# DM35_Power_C_V1_0.net
KiCad netlist of a schematic drawn in Altium Designer
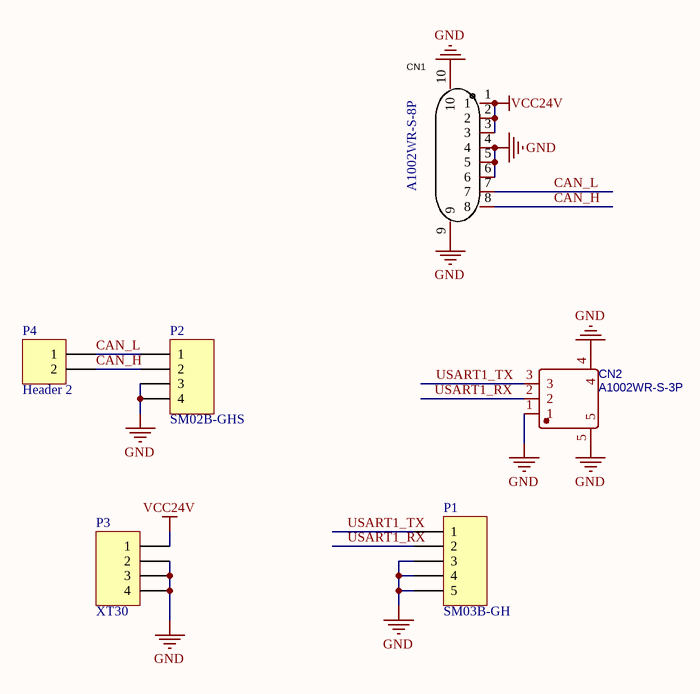
[diagram p0: DM35_Power_C_V1.0.SchDoc]

(export (version "E")
  (design (tool "Eeschema 10.0.6"))
  (components
    (comp (ref "CN1")
      (value "A1002WR-S-8P")
      (footprint "CONN-SMD_A1002WR-S-8P")
      (fields (field (name "MANUFACTURER") "CJT(长江连接器)"))
      (libsource (lib "dm-sch_library") (part "A1002WR-S-8P"))
    )
    (comp (ref "CN2")
      (value "A1002WR-S-3P")
      (footprint "CONN-SMD_A1002WR-S-3P")
      (fields (field (name "BOM_SUPPLIER PART") "C239521") (field (name "CONTRIBUTOR") "LCSC"))
      (libsource (lib "dm-sch_library") (part "A1002WR-S-3P"))
    )
    (comp (ref "P1")
      (value "SM03B-GH")
      (footprint "JST SM03B-GHS-TB")
      (description "Header, 5-Pin")
      (fields (field (name "PUBLISHER") "Altium Limited"))
      (libsource (lib "Miscellaneous Connectors") (part "Header 5"))
    )
    (comp (ref "P2")
      (value "SM02B-GHS")
      (footprint "JST-SM02B-GHS-TB")
      (description "Header, 4-Pin")
      (fields (field (name "PUBLISHER") "Altium Limited"))
      (libsource (lib "Miscellaneous Connectors") (part "Header 4"))
    )
    (comp (ref "P3")
      (value "XT30")
      (footprint "XT30PW-M")
      (description "Header, 4-Pin")
      (fields (field (name "PUBLISHER") "Altium Limited"))
      (libsource (lib "") (part "Header 4_1"))
    )
    (comp (ref "P4")
      (value "Header 2")
      (footprint "HDR1X2")
      (description "Header, 2-Pin")
      (fields (field (name "PUBLISHER") "Altium Limited"))
      (libsource (lib "Miscellaneous Connectors") (part "Header 2"))
    )
  )
  (nets
    (net (code "1") (name "/CAN_H") (class "Default")
      (node (ref "CN1") (pin "8") (pinfunction "8_8") (pintype "passive"))
      (node (ref "P2") (pin "2") (pinfunction "2_2") (pintype "passive"))
      (node (ref "P4") (pin "2") (pinfunction "2_2") (pintype "passive"))
    )
    (net (code "2") (name "/CAN_L") (class "Default")
      (node (ref "CN1") (pin "7") (pinfunction "7_7") (pintype "passive"))
      (node (ref "P2") (pin "1") (pinfunction "1_1") (pintype "passive"))
      (node (ref "P4") (pin "1") (pinfunction "1_1") (pintype "passive"))
    )
    (net (code "3") (name "/USART1_RX") (class "Default")
      (node (ref "CN2") (pin "2") (pinfunction "2_2") (pintype "passive"))
      (node (ref "P1") (pin "2") (pinfunction "2_2") (pintype "passive"))
    )
    (net (code "4") (name "/USART1_TX") (class "Default")
      (node (ref "CN2") (pin "3") (pinfunction "3_3") (pintype "passive"))
      (node (ref "P1") (pin "1") (pinfunction "1_1") (pintype "passive"))
    )
    (net (code "5") (name "GND") (class "Default")
      (node (ref "CN1") (pin "10") (pinfunction "10_10") (pintype "passive"))
      (node (ref "CN1") (pin "4") (pinfunction "4_4") (pintype "passive"))
      (node (ref "CN1") (pin "5") (pinfunction "5_5") (pintype "passive"))
      (node (ref "CN1") (pin "6") (pinfunction "6_6") (pintype "passive"))
      (node (ref "CN1") (pin "9") (pinfunction "9_9") (pintype "passive"))
      (node (ref "CN2") (pin "1") (pinfunction "1_1") (pintype "passive"))
      (node (ref "CN2") (pin "4") (pinfunction "4_4") (pintype "passive"))
      (node (ref "CN2") (pin "5") (pinfunction "5_5") (pintype "passive"))
      (node (ref "P1") (pin "3") (pinfunction "3_3") (pintype "passive"))
      (node (ref "P1") (pin "4") (pinfunction "4_4") (pintype "passive"))
      (node (ref "P1") (pin "5") (pinfunction "5_5") (pintype "passive"))
      (node (ref "P2") (pin "3") (pinfunction "3_3") (pintype "passive"))
      (node (ref "P2") (pin "4") (pinfunction "4_4") (pintype "passive"))
      (node (ref "P3") (pin "2") (pinfunction "2_2") (pintype "passive"))
      (node (ref "P3") (pin "3") (pinfunction "3_3") (pintype "passive"))
      (node (ref "P3") (pin "4") (pinfunction "4_4") (pintype "passive"))
    )
    (net (code "6") (name "VCC24V") (class "Default")
      (node (ref "CN1") (pin "1") (pinfunction "1_1") (pintype "passive"))
      (node (ref "CN1") (pin "2") (pinfunction "2_2") (pintype "passive"))
      (node (ref "CN1") (pin "3") (pinfunction "3_3") (pintype "passive"))
      (node (ref "P3") (pin "1") (pinfunction "1_1") (pintype "passive"))
    )
  )
)
